# 51.net
KiCad netlist of a schematic drawn in EasyEDA Pro
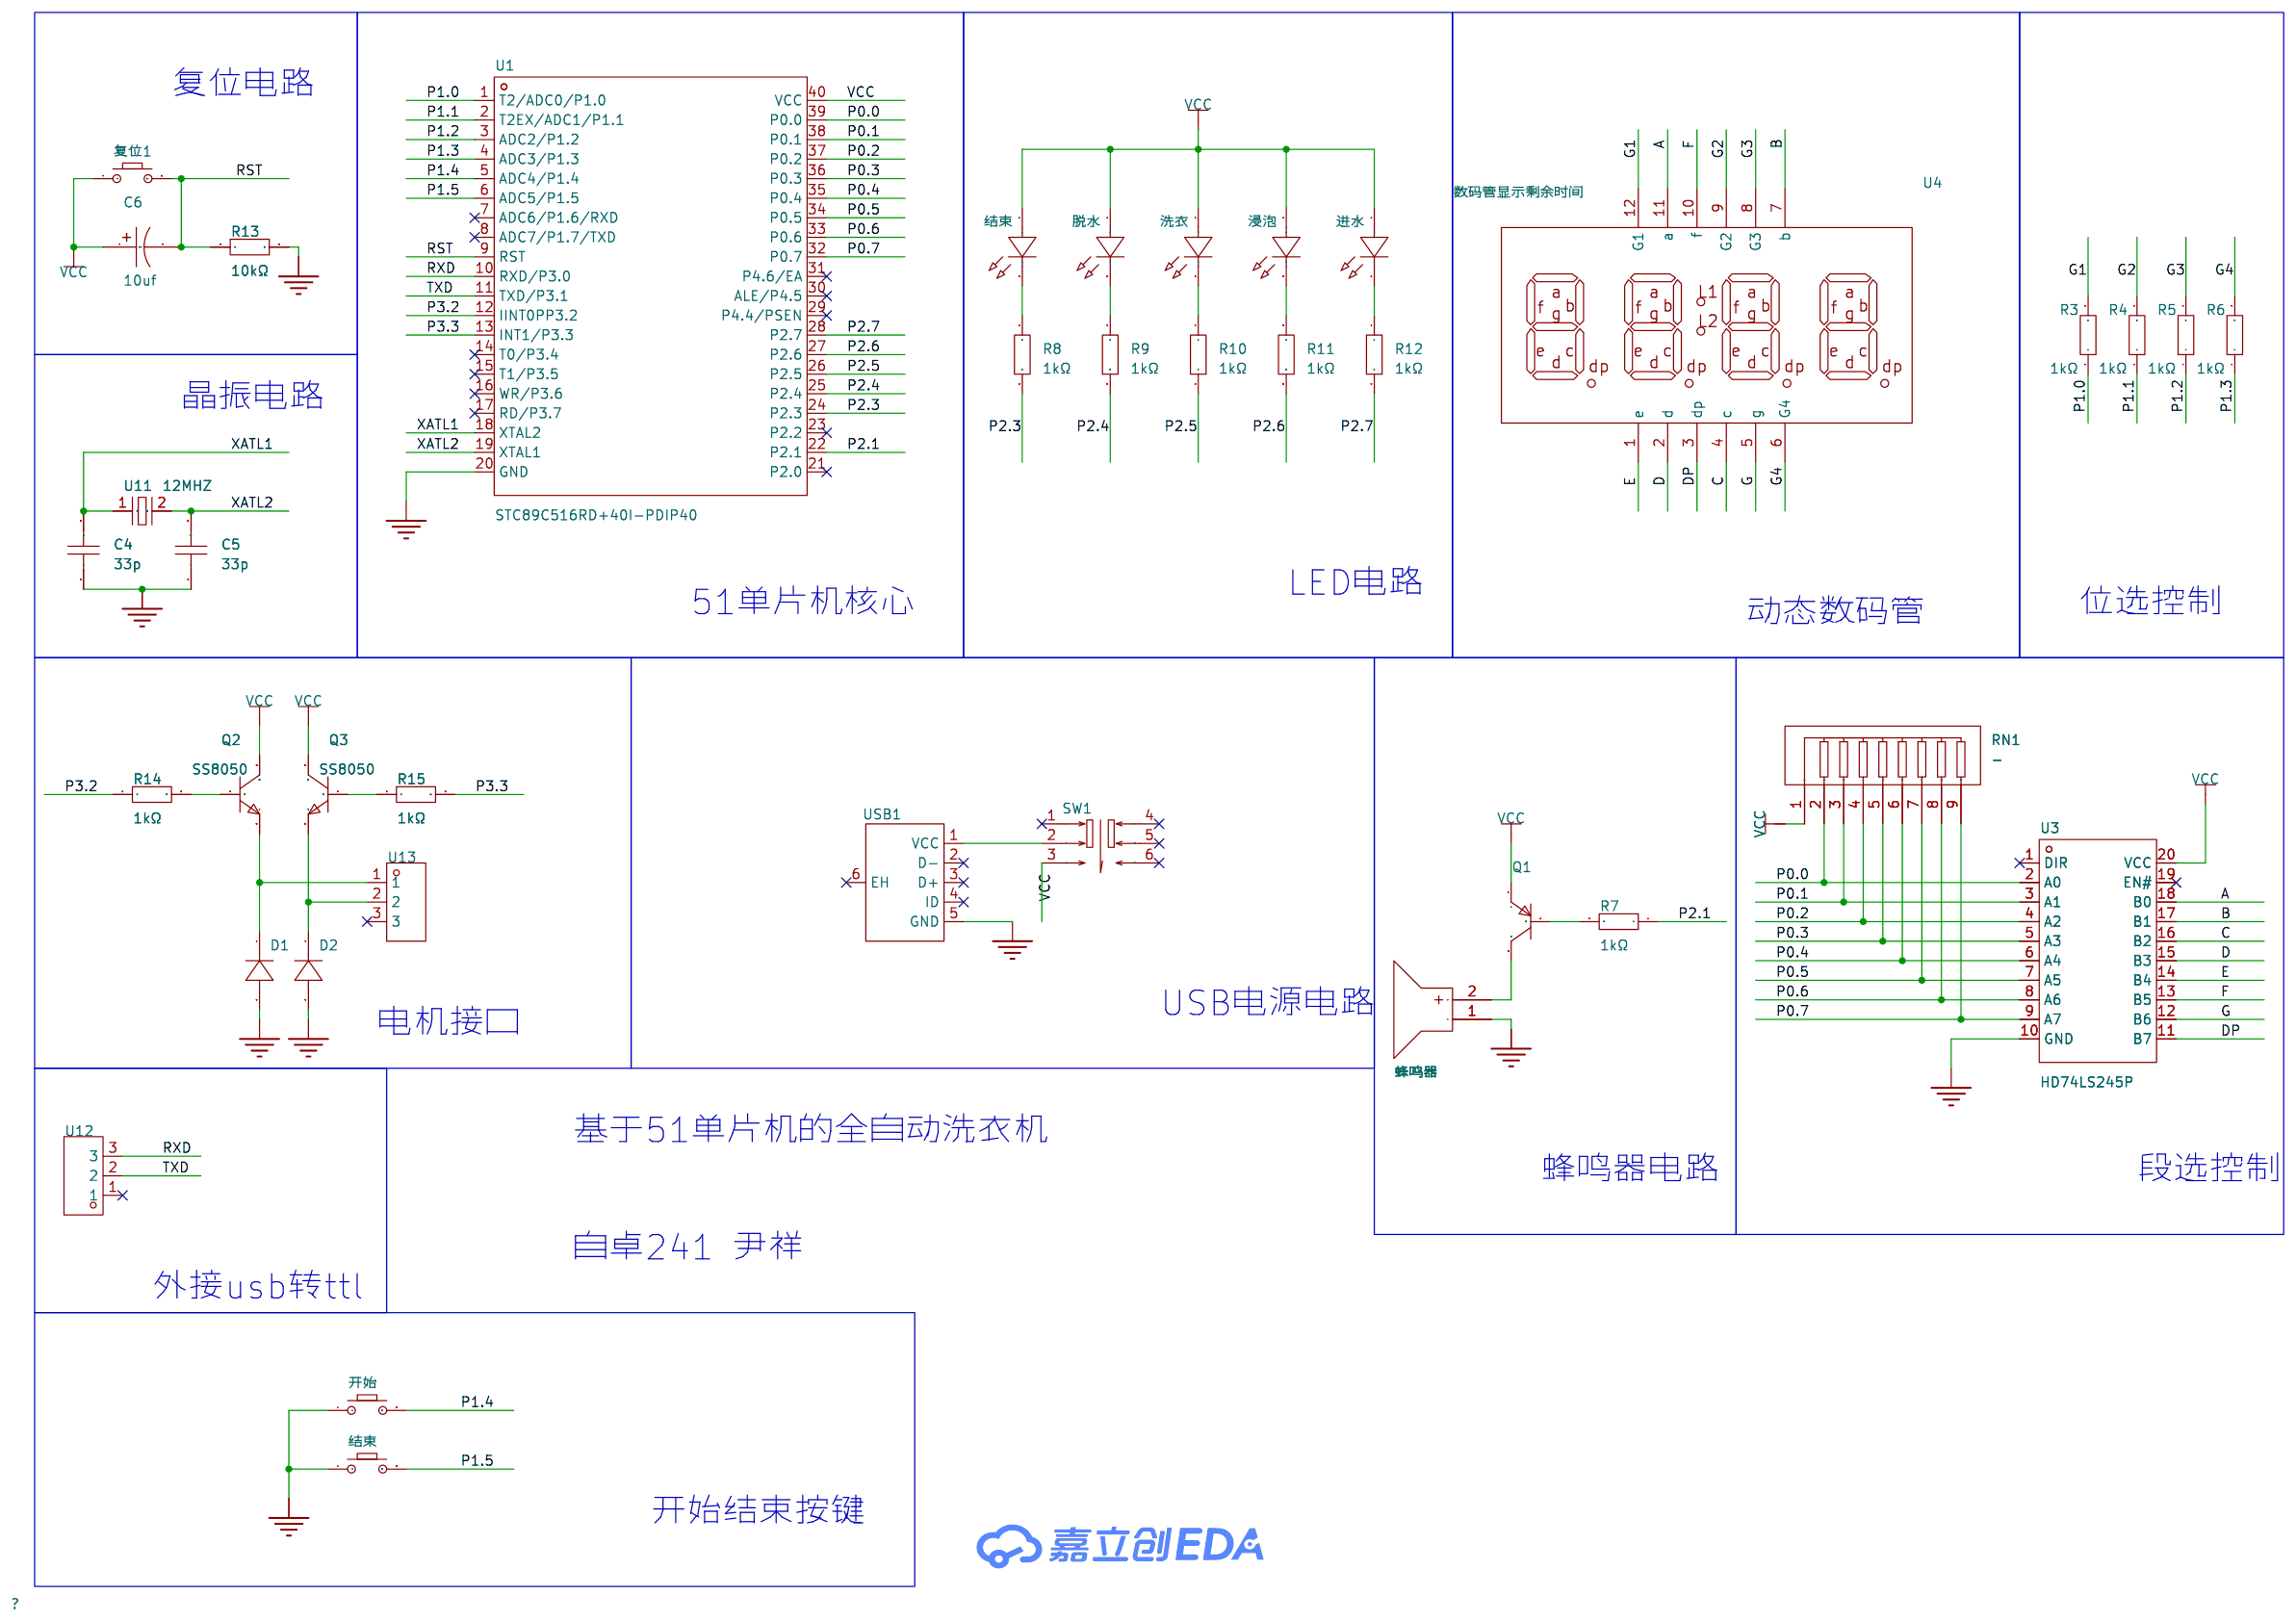
[diagram p0: schematic sheet]

(export (version "E")
  (design (tool "Eeschema 10.0.6"))
  (components
    (comp (ref "C4")
      (value "33p")
      (footprint "easyedapro:CAP-TH_L10.0-W4.5-P7.50-D0.6")
      (description "容值:-;额定电压:-;")
      (fields (field (name "Manufacturer Part") "250V 0.1uF 5% CBB电容"))
      (libsource (lib "easyedapro") (part "250V 0.1UF 5% CBBCapacitor"))
    )
    (comp (ref "C5")
      (value "33p")
      (footprint "easyedapro:CAP-TH_L10.0-W4.5-P7.50-D0.6")
      (description "容值:-;额定电压:-;")
      (fields (field (name "Manufacturer Part") "250V 0.1uF 5% CBB电容"))
      (libsource (lib "easyedapro") (part "250V 0.1UF 5% CBBCapacitor"))
    )
    (comp (ref "C6")
      (value "10uf")
      (footprint "easyedapro:CAP-TH_BD10.0-P5.00-D0.6-FD")
      (libsource (lib "easyedapro") (part "LF221M1HBKJ1013VGN"))
    )
    (comp (ref "D1")
      (value "~")
      (footprint "easyedapro:DO_1N4007")
      (libsource (lib "easyedapro") (part "D_1N4007"))
    )
    (comp (ref "D2")
      (value "~")
      (footprint "easyedapro:DO_1N4007")
      (libsource (lib "easyedapro") (part "D_1N4007"))
    )
    (comp (ref "Q1")
      (value "~")
      (footprint "easyedapro:S8550P_TO-92")
      (libsource (lib "easyedapro") (part "S8550_TO_PNP"))
    )
    (comp (ref "Q2")
      (value "SS8050")
      (footprint "easyedapro:SOT-23-3_L2.9-W1.3-P1.90-LS2.4-BR")
      (description "晶体管类型:NPN;集电极电流(Ic):1.5A;集射极击穿电压(Vceo):25V;功率(Pd):300mW;直流电流增益(hFE@Ic,Vce):200@800mA,1V;")
      (fields (field (name "Manufacturer") "CJ(江苏长电/长晶)"))
      (libsource (lib "easyedapro") (part "SS8050_C2150"))
    )
    (comp (ref "Q3")
      (value "SS8050")
      (footprint "easyedapro:SOT-23-3_L2.9-W1.3-P1.90-LS2.4-BR")
      (description "晶体管类型:NPN;集电极电流(Ic):1.5A;集射极击穿电压(Vceo):25V;功率(Pd):300mW;直流电流增益(hFE@Ic,Vce):200@800mA,1V;")
      (fields (field (name "Manufacturer") "CJ(江苏长电/长晶)"))
      (libsource (lib "easyedapro") (part "SS8050_C2150"))
    )
    (comp (ref "R3")
      (value "1kΩ")
      (footprint "easyedapro:Res_1/8W")
      (libsource (lib "easyedapro") (part "电阻"))
    )
    (comp (ref "R4")
      (value "1kΩ")
      (footprint "easyedapro:Res_1/8W")
      (libsource (lib "easyedapro") (part "电阻"))
    )
    (comp (ref "R5")
      (value "1kΩ")
      (footprint "easyedapro:Res_1/8W")
      (libsource (lib "easyedapro") (part "电阻"))
    )
    (comp (ref "R6")
      (value "1kΩ")
      (footprint "easyedapro:Res_1/8W")
      (libsource (lib "easyedapro") (part "电阻"))
    )
    (comp (ref "R7")
      (value "1kΩ")
      (footprint "easyedapro:Res_1/8W")
      (libsource (lib "easyedapro") (part "电阻"))
    )
    (comp (ref "R8")
      (value "1kΩ")
      (footprint "easyedapro:Res_1/8W")
      (libsource (lib "easyedapro") (part "电阻"))
    )
    (comp (ref "R9")
      (value "1kΩ")
      (footprint "easyedapro:Res_1/8W")
      (libsource (lib "easyedapro") (part "电阻"))
    )
    (comp (ref "R10")
      (value "1kΩ")
      (footprint "easyedapro:Res_1/8W")
      (libsource (lib "easyedapro") (part "电阻"))
    )
    (comp (ref "R11")
      (value "1kΩ")
      (footprint "easyedapro:Res_1/8W")
      (libsource (lib "easyedapro") (part "电阻"))
    )
    (comp (ref "R12")
      (value "1kΩ")
      (footprint "easyedapro:Res_1/8W")
      (libsource (lib "easyedapro") (part "电阻"))
    )
    (comp (ref "R13")
      (value "10kΩ")
      (footprint "easyedapro:Res_1/8W")
      (libsource (lib "easyedapro") (part "电阻"))
    )
    (comp (ref "R14")
      (value "1kΩ")
      (footprint "easyedapro:Res_1/8W")
      (libsource (lib "easyedapro") (part "电阻"))
    )
    (comp (ref "R15")
      (value "1kΩ")
      (footprint "easyedapro:Res_1/8W")
      (libsource (lib "easyedapro") (part "电阻"))
    )
    (comp (ref "RN1")
      (value "-")
      (footprint "easyedapro:RES-ARRAY-TH_9P-P2.54-D1.0")
      (description "电阻器数:-;阻值:-;单个元件功率:-;")
      (fields (field (name "Manufacturer Part") "排阻 10 K 5%"))
      (libsource (lib "easyedapro") (part "10 K 5%"))
    )
    (comp (ref "SW1")
      (value "SP-2212")
      (footprint "easyedapro:SW-TH_6P-L7.2-W7.2-P2.00-LS5.0")
      (description "电路结构:双刀双掷;自锁/无锁:自锁;安装方式:直插;触点电流:100mA;额定电压 (DC):30V;作用力:230gf;机械寿命:1.2万次;")
      (fields (field (name "Manufacturer") "RISHENG(日昇)"))
      (libsource (lib "easyedapro") (part "SP-2212"))
    )
    (comp (ref "U1")
      (value "STC89C516RD+40I-PDIP40")
      (footprint "easyedapro:DIP-40_L52.3-W13.9-P2.54-LS15.2-BL")
      (description "CPU内核:51系列;程序存储容量:61KB;RAM总容量:1.25KB;GPIO端口数量:35;工作电压范围:3.5V~5.5V;CPU最大主频:-;程序存储器类型:FLASH;")
      (fields (field (name "Manufacturer") "STC(宏晶)"))
      (libsource (lib "easyedapro") (part "STC89C516RD+40I-PDIP40"))
    )
    (comp (ref "U3")
      (value "HD74LS245P")
      (footprint "easyedapro:DIP-20_L26.8-W6.4-P2.54-LS7.6-BL")
      (fields (field (name "Manufacturer") "RENESAS(瑞萨)/IDT"))
      (libsource (lib "easyedapro") (part "HD74LS245P"))
    )
    (comp (ref "U4")
      (value "数码管显示剩余时间")
      (footprint "easyedapro:LED-SEG-TH_12P-L32.1-W10.0-P12.7-S7.62-BL")
      (libsource (lib "easyedapro") (part "0.28 4位 数码管"))
    )
    (comp (ref "U11")
      (value "12MHZ")
      (footprint "easyedapro:HC-49S_L11.0-W4.7-P4.88")
      (libsource (lib "easyedapro") (part "直插晶振"))
    )
    (comp (ref "U12")
      (value "2.54MM间距单排插针3P/高度11mm")
      (footprint "easyedapro:HDR-TH_3P-P2.54-V-M")
      (libsource (lib "easyedapro") (part "2.54MM间距单排插针3P/高度11MM"))
    )
    (comp (ref "U13")
      (value "2.54MM间距单排插针3P/高度11mm")
      (footprint "easyedapro:HDR-TH_3P-P2.54-V-M")
      (libsource (lib "easyedapro") (part "2.54MM间距单排插针3P/高度11MM"))
    )
    (comp (ref "USB1")
      (value "~")
      (footprint "easyedapro:USB_Micro")
      (libsource (lib "easyedapro") (part "USB_Micro"))
    )
    (comp (ref "图书馆1")
      (value "脱水")
      (footprint "easyedapro:LED-TH_BD3.0-P2.54-FD")
      (libsource (lib "easyedapro") (part "3MMFIR"))
    )
    (comp (ref "复位1")
      (value "~")
      (footprint "easyedapro:Key_TH_3.5x6x4.3")
      (libsource (lib "easyedapro") (part "Key_TH_3.5x6x4.3"))
    )
    (comp (ref "学生宿舍1")
      (value "洗衣")
      (footprint "easyedapro:LED-TH_BD3.0-P2.54-FD")
      (libsource (lib "easyedapro") (part "3MMFIR"))
    )
    (comp (ref "开始")
      (value "~")
      (footprint "easyedapro:Key_TH_3.5x6x4.3")
      (libsource (lib "easyedapro") (part "Key_TH_3.5x6x4.3"))
    )
    (comp (ref "打铃1")
      (value "蜂鸣器")
      (footprint "easyedapro:BUZ-TH_BD12.0-P6.00-D0.9-RD")
      (fields (field (name "Manufacturer Part") "打铃"))
      (libsource (lib "easyedapro") (part "BUZZER"))
    )
    (comp (ref "教十楼1")
      (value "浸泡")
      (footprint "easyedapro:LED-TH_BD3.0-P2.54-FD")
      (libsource (lib "easyedapro") (part "3MMFIR"))
    )
    (comp (ref "结束")
      (value "~")
      (footprint "easyedapro:Key_TH_3.5x6x4.3")
      (libsource (lib "easyedapro") (part "Key_TH_3.5x6x4.3"))
    )
    (comp (ref "综合南楼1")
      (value "进水")
      (footprint "easyedapro:LED-TH_BD3.0-P2.54-FD")
      (libsource (lib "easyedapro") (part "3MMFIR"))
    )
    (comp (ref "路灯1")
      (value "结束")
      (footprint "easyedapro:LED-TH_BD3.0-P2.54-FD")
      (libsource (lib "easyedapro") (part "3MMFIR"))
    )
  )
  (nets
    (net (code "1") (name "/A") (class "Default")
      (node (ref "U3") (pin "18") (pinfunction "B0_18") (pintype "unspecified"))
      (node (ref "U4") (pin "11") (pinfunction "a_11") (pintype "input"))
    )
    (net (code "2") (name "/B") (class "Default")
      (node (ref "U3") (pin "17") (pinfunction "B1_17") (pintype "unspecified"))
      (node (ref "U4") (pin "7") (pinfunction "b_7") (pintype "input"))
    )
    (net (code "3") (name "/C") (class "Default")
      (node (ref "U3") (pin "16") (pinfunction "B2_16") (pintype "unspecified"))
      (node (ref "U4") (pin "4") (pinfunction "c_4") (pintype "input"))
    )
    (net (code "4") (name "/D") (class "Default")
      (node (ref "U3") (pin "15") (pinfunction "B3_15") (pintype "unspecified"))
      (node (ref "U4") (pin "2") (pinfunction "d_2") (pintype "input"))
    )
    (net (code "5") (name "/DP") (class "Default")
      (node (ref "U3") (pin "11") (pinfunction "B7_11") (pintype "unspecified"))
      (node (ref "U4") (pin "3") (pinfunction "dp_3") (pintype "input"))
    )
    (net (code "6") (name "/E") (class "Default")
      (node (ref "U3") (pin "14") (pinfunction "B4_14") (pintype "unspecified"))
      (node (ref "U4") (pin "1") (pinfunction "e_1") (pintype "input"))
    )
    (net (code "7") (name "/F") (class "Default")
      (node (ref "U3") (pin "13") (pinfunction "B5_13") (pintype "unspecified"))
      (node (ref "U4") (pin "10") (pinfunction "f_10") (pintype "input"))
    )
    (net (code "8") (name "/G") (class "Default")
      (node (ref "U3") (pin "12") (pinfunction "B6_12") (pintype "unspecified"))
      (node (ref "U4") (pin "5") (pinfunction "g_5") (pintype "input"))
    )
    (net (code "9") (name "/G1") (class "Default")
      (node (ref "R3") (pin "2") (pinfunction "2_2") (pintype "input"))
      (node (ref "U4") (pin "12") (pinfunction "G1_12") (pintype "input"))
    )
    (net (code "10") (name "/G2") (class "Default")
      (node (ref "R4") (pin "2") (pinfunction "2_2") (pintype "input"))
      (node (ref "U4") (pin "9") (pinfunction "G2_9") (pintype "input"))
    )
    (net (code "11") (name "/G3") (class "Default")
      (node (ref "R5") (pin "2") (pinfunction "2_2") (pintype "input"))
      (node (ref "U4") (pin "8") (pinfunction "G3_8") (pintype "input"))
    )
    (net (code "12") (name "/G4") (class "Default")
      (node (ref "R6") (pin "2") (pinfunction "2_2") (pintype "input"))
      (node (ref "U4") (pin "6") (pinfunction "G4_6") (pintype "input"))
    )
    (net (code "13") (name "/P0.0") (class "Default")
      (node (ref "RN1") (pin "2") (pinfunction "2_2") (pintype "input"))
      (node (ref "U1") (pin "39") (pinfunction "P0.0_39") (pintype "unspecified"))
      (node (ref "U3") (pin "2") (pinfunction "A0_2") (pintype "unspecified"))
    )
    (net (code "14") (name "/P0.1") (class "Default")
      (node (ref "RN1") (pin "3") (pinfunction "3_3") (pintype "input"))
      (node (ref "U1") (pin "38") (pinfunction "P0.1_38") (pintype "unspecified"))
      (node (ref "U3") (pin "3") (pinfunction "A1_3") (pintype "unspecified"))
    )
    (net (code "15") (name "/P0.2") (class "Default")
      (node (ref "RN1") (pin "4") (pinfunction "4_4") (pintype "input"))
      (node (ref "U1") (pin "37") (pinfunction "P0.2_37") (pintype "unspecified"))
      (node (ref "U3") (pin "4") (pinfunction "A2_4") (pintype "unspecified"))
    )
    (net (code "16") (name "/P0.3") (class "Default")
      (node (ref "RN1") (pin "5") (pinfunction "5_5") (pintype "input"))
      (node (ref "U1") (pin "36") (pinfunction "P0.3_36") (pintype "unspecified"))
      (node (ref "U3") (pin "5") (pinfunction "A3_5") (pintype "unspecified"))
    )
    (net (code "17") (name "/P0.4") (class "Default")
      (node (ref "RN1") (pin "6") (pinfunction "6_6") (pintype "input"))
      (node (ref "U1") (pin "35") (pinfunction "P0.4_35") (pintype "unspecified"))
      (node (ref "U3") (pin "6") (pinfunction "A4_6") (pintype "unspecified"))
    )
    (net (code "18") (name "/P0.5") (class "Default")
      (node (ref "RN1") (pin "7") (pinfunction "7_7") (pintype "input"))
      (node (ref "U1") (pin "34") (pinfunction "P0.5_34") (pintype "unspecified"))
      (node (ref "U3") (pin "7") (pinfunction "A5_7") (pintype "unspecified"))
    )
    (net (code "19") (name "/P0.6") (class "Default")
      (node (ref "RN1") (pin "8") (pinfunction "8_8") (pintype "input"))
      (node (ref "U1") (pin "33") (pinfunction "P0.6_33") (pintype "unspecified"))
      (node (ref "U3") (pin "8") (pinfunction "A6_8") (pintype "unspecified"))
    )
    (net (code "20") (name "/P0.7") (class "Default")
      (node (ref "RN1") (pin "9") (pinfunction "9_9") (pintype "input"))
      (node (ref "U1") (pin "32") (pinfunction "P0.7_32") (pintype "unspecified"))
      (node (ref "U3") (pin "9") (pinfunction "A7_9") (pintype "unspecified"))
    )
    (net (code "21") (name "/P1.0") (class "Default")
      (node (ref "R3") (pin "1") (pinfunction "1_1") (pintype "input"))
      (node (ref "U1") (pin "1") (pinfunction "T2/ADC0/P1.0_1") (pintype "unspecified"))
    )
    (net (code "22") (name "/P1.1") (class "Default")
      (node (ref "R4") (pin "1") (pinfunction "1_1") (pintype "input"))
      (node (ref "U1") (pin "2") (pinfunction "T2EX/ADC1/P1.1_2") (pintype "unspecified"))
    )
    (net (code "23") (name "/P1.2") (class "Default")
      (node (ref "R5") (pin "1") (pinfunction "1_1") (pintype "input"))
      (node (ref "U1") (pin "3") (pinfunction "ADC2/P1.2_3") (pintype "unspecified"))
    )
    (net (code "24") (name "/P1.3") (class "Default")
      (node (ref "R6") (pin "1") (pinfunction "1_1") (pintype "input"))
      (node (ref "U1") (pin "4") (pinfunction "ADC3/P1.3_4") (pintype "unspecified"))
    )
    (net (code "25") (name "/P1.4") (class "Default")
      (node (ref "U1") (pin "5") (pinfunction "ADC4/P1.4_5") (pintype "unspecified"))
      (node (ref "开始") (pin "B") (pinfunction "B_B") (pintype "input"))
    )
    (net (code "26") (name "/P1.5") (class "Default")
      (node (ref "U1") (pin "6") (pinfunction "ADC5/P1.5_6") (pintype "unspecified"))
      (node (ref "结束") (pin "B") (pinfunction "B_B") (pintype "input"))
    )
    (net (code "27") (name "/P2.1") (class "Default")
      (node (ref "R7") (pin "1") (pinfunction "1_1") (pintype "input"))
      (node (ref "U1") (pin "22") (pinfunction "P2.1_22") (pintype "unspecified"))
    )
    (net (code "28") (name "/P2.3") (class "Default")
      (node (ref "R8") (pin "2") (pinfunction "2_2") (pintype "input"))
      (node (ref "U1") (pin "24") (pinfunction "P2.3_24") (pintype "unspecified"))
    )
    (net (code "29") (name "/P2.4") (class "Default")
      (node (ref "R9") (pin "2") (pinfunction "2_2") (pintype "input"))
      (node (ref "U1") (pin "25") (pinfunction "P2.4_25") (pintype "unspecified"))
    )
    (net (code "30") (name "/P2.5") (class "Default")
      (node (ref "R10") (pin "2") (pinfunction "2_2") (pintype "input"))
      (node (ref "U1") (pin "26") (pinfunction "P2.5_26") (pintype "unspecified"))
    )
    (net (code "31") (name "/P2.6") (class "Default")
      (node (ref "R11") (pin "2") (pinfunction "2_2") (pintype "input"))
      (node (ref "U1") (pin "27") (pinfunction "P2.6_27") (pintype "unspecified"))
    )
    (net (code "32") (name "/P2.7") (class "Default")
      (node (ref "R12") (pin "2") (pinfunction "2_2") (pintype "input"))
      (node (ref "U1") (pin "28") (pinfunction "P2.7_28") (pintype "unspecified"))
    )
    (net (code "33") (name "/P3.2") (class "Default")
      (node (ref "R14") (pin "1") (pinfunction "1_1") (pintype "input"))
      (node (ref "U1") (pin "12") (pinfunction "IINT0PP3.2_12") (pintype "unspecified"))
    )
    (net (code "34") (name "/P3.3") (class "Default")
      (node (ref "R15") (pin "2") (pinfunction "2_2") (pintype "input"))
      (node (ref "U1") (pin "13") (pinfunction "INT1/P3.3_13") (pintype "unspecified"))
    )
    (net (code "35") (name "/RST") (class "Default")
      (node (ref "C6") (pin "2") (pinfunction "2_2") (pintype "unspecified"))
      (node (ref "R13") (pin "1") (pinfunction "1_1") (pintype "input"))
      (node (ref "U1") (pin "9") (pinfunction "RST_9") (pintype "unspecified"))
      (node (ref "复位1") (pin "B") (pinfunction "B_B") (pintype "input"))
    )
    (net (code "36") (name "/RXD") (class "Default")
      (node (ref "U1") (pin "10") (pinfunction "RXD/P3.0_10") (pintype "unspecified"))
      (node (ref "U12") (pin "3") (pinfunction "3_3") (pintype "unspecified"))
    )
    (net (code "37") (name "/TXD") (class "Default")
      (node (ref "U1") (pin "11") (pinfunction "TXD/P3.1_11") (pintype "unspecified"))
      (node (ref "U12") (pin "2") (pinfunction "2_2") (pintype "unspecified"))
    )
    (net (code "38") (name "/XATL1") (class "Default")
      (node (ref "C4") (pin "2") (pinfunction "2_2") (pintype "unspecified"))
      (node (ref "U1") (pin "18") (pinfunction "XTAL2_18") (pintype "unspecified"))
      (node (ref "U11") (pin "1") (pinfunction "1_1") (pintype "input"))
    )
    (net (code "39") (name "/XATL2") (class "Default")
      (node (ref "C5") (pin "2") (pinfunction "2_2") (pintype "unspecified"))
      (node (ref "U1") (pin "19") (pinfunction "XTAL1_19") (pintype "unspecified"))
      (node (ref "U11") (pin "2") (pinfunction "GND_2") (pintype "input"))
    )
    (net (code "40") (name "GND") (class "Default")
      (node (ref "C4") (pin "1") (pinfunction "1_1") (pintype "unspecified"))
      (node (ref "C5") (pin "1") (pinfunction "1_1") (pintype "unspecified"))
      (node (ref "D1") (pin "2") (pinfunction "A_2") (pintype "input"))
      (node (ref "D2") (pin "2") (pinfunction "A_2") (pintype "input"))
      (node (ref "R13") (pin "2") (pinfunction "2_2") (pintype "input"))
      (node (ref "U1") (pin "20") (pinfunction "GND_20") (pintype "unspecified"))
      (node (ref "U3") (pin "10") (pinfunction "GND_10") (pintype "unspecified"))
      (node (ref "USB1") (pin "5") (pinfunction "GND_5") (pintype "input"))
      (node (ref "开始") (pin "A") (pinfunction "A_A") (pintype "input"))
      (node (ref "打铃1") (pin "1") (pinfunction "-_1") (pintype "unspecified"))
      (node (ref "结束") (pin "A") (pinfunction "A_A") (pintype "input"))
    )
    (net (code "41") (name "Net-(D1-K)") (class "Default")
      (node (ref "D1") (pin "1") (pinfunction "K_1") (pintype "input"))
      (node (ref "Q2") (pin "2") (pinfunction "E_2") (pintype "unspecified"))
      (node (ref "U13") (pin "1") (pinfunction "1_1") (pintype "unspecified"))
    )
    (net (code "42") (name "Net-(D2-K)") (class "Default")
      (node (ref "D2") (pin "1") (pinfunction "K_1") (pintype "input"))
      (node (ref "Q3") (pin "2") (pinfunction "E_2") (pintype "unspecified"))
      (node (ref "U13") (pin "2") (pinfunction "2_2") (pintype "unspecified"))
    )
    (net (code "43") (name "Net-(Q1-B)") (class "Default")
      (node (ref "Q1") (pin "2") (pinfunction "B_2") (pintype "input"))
      (node (ref "R7") (pin "2") (pinfunction "2_2") (pintype "input"))
    )
    (net (code "44") (name "Net-(Q1-C)") (class "Default")
      (node (ref "Q1") (pin "3") (pinfunction "C_3") (pintype "input"))
      (node (ref "打铃1") (pin "2") (pinfunction "+_2") (pintype "unspecified"))
    )
    (net (code "45") (name "Net-(Q2-B)") (class "Default")
      (node (ref "Q2") (pin "1") (pinfunction "B_1") (pintype "unspecified"))
      (node (ref "R14") (pin "2") (pinfunction "2_2") (pintype "input"))
    )
    (net (code "46") (name "Net-(Q3-B)") (class "Default")
      (node (ref "Q3") (pin "1") (pinfunction "B_1") (pintype "unspecified"))
      (node (ref "R15") (pin "1") (pinfunction "1_1") (pintype "input"))
    )
    (net (code "47") (name "Net-(USB1-VCC)") (class "Default")
      (node (ref "SW1") (pin "2") (pinfunction "2_2") (pintype "unspecified"))
      (node (ref "USB1") (pin "1") (pinfunction "VCC_1") (pintype "input"))
    )
    (net (code "48") (name "Net-(图书馆1-K)") (class "Default")
      (node (ref "R9") (pin "1") (pinfunction "1_1") (pintype "input"))
      (node (ref "图书馆1") (pin "2") (pinfunction "K_2") (pintype "unspecified"))
    )
    (net (code "49") (name "Net-(学生宿舍1-K)") (class "Default")
      (node (ref "R10") (pin "1") (pinfunction "1_1") (pintype "input"))
      (node (ref "学生宿舍1") (pin "2") (pinfunction "K_2") (pintype "unspecified"))
    )
    (net (code "50") (name "Net-(教十楼1-K)") (class "Default")
      (node (ref "R11") (pin "1") (pinfunction "1_1") (pintype "input"))
      (node (ref "教十楼1") (pin "2") (pinfunction "K_2") (pintype "unspecified"))
    )
    (net (code "51") (name "Net-(综合南楼1-K)") (class "Default")
      (node (ref "R12") (pin "1") (pinfunction "1_1") (pintype "input"))
      (node (ref "综合南楼1") (pin "2") (pinfunction "K_2") (pintype "unspecified"))
    )
    (net (code "52") (name "Net-(路灯1-K)") (class "Default")
      (node (ref "R8") (pin "1") (pinfunction "1_1") (pintype "input"))
      (node (ref "路灯1") (pin "2") (pinfunction "K_2") (pintype "unspecified"))
    )
    (net (code "53") (name "VCC") (class "Default")
      (node (ref "C6") (pin "1") (pinfunction "1_1") (pintype "unspecified"))
      (node (ref "Q1") (pin "1") (pinfunction "E_1") (pintype "input"))
      (node (ref "Q2") (pin "3") (pinfunction "C_3") (pintype "unspecified"))
      (node (ref "Q3") (pin "3") (pinfunction "C_3") (pintype "unspecified"))
      (node (ref "RN1") (pin "1") (pinfunction "1_1") (pintype "input"))
      (node (ref "SW1") (pin "3") (pinfunction "3_3") (pintype "unspecified"))
      (node (ref "U1") (pin "40") (pinfunction "VCC_40") (pintype "unspecified"))
      (node (ref "U3") (pin "20") (pinfunction "VCC_20") (pintype "unspecified"))
      (node (ref "图书馆1") (pin "1") (pinfunction "A_1") (pintype "unspecified"))
      (node (ref "复位1") (pin "A") (pinfunction "A_A") (pintype "input"))
      (node (ref "学生宿舍1") (pin "1") (pinfunction "A_1") (pintype "unspecified"))
      (node (ref "教十楼1") (pin "1") (pinfunction "A_1") (pintype "unspecified"))
      (node (ref "综合南楼1") (pin "1") (pinfunction "A_1") (pintype "unspecified"))
      (node (ref "路灯1") (pin "1") (pinfunction "A_1") (pintype "unspecified"))
    )
    (net (code "54") (name "unconnected-(SW1-Pad1)") (class "Default")
      (node (ref "SW1") (pin "1") (pinfunction "1_1") (pintype "unspecified+no_connect"))
    )
    (net (code "55") (name "unconnected-(SW1-Pad4)") (class "Default")
      (node (ref "SW1") (pin "4") (pinfunction "4_4") (pintype "unspecified+no_connect"))
    )
    (net (code "56") (name "unconnected-(SW1-Pad5)") (class "Default")
      (node (ref "SW1") (pin "5") (pinfunction "5_5") (pintype "unspecified+no_connect"))
    )
    (net (code "57") (name "unconnected-(SW1-Pad6)") (class "Default")
      (node (ref "SW1") (pin "6") (pinfunction "6_6") (pintype "unspecified+no_connect"))
    )
    (net (code "58") (name "unconnected-(U1-ADC6{slash}P1.6{slash}RXD-Pad7)") (class "Default")
      (node (ref "U1") (pin "7") (pinfunction "ADC6/P1.6/RXD_7") (pintype "unspecified+no_connect"))
    )
    (net (code "59") (name "unconnected-(U1-ADC7{slash}P1.7{slash}TXD-Pad8)") (class "Default")
      (node (ref "U1") (pin "8") (pinfunction "ADC7/P1.7/TXD_8") (pintype "unspecified+no_connect"))
    )
    (net (code "60") (name "unconnected-(U1-ALE{slash}P4.5-Pad30)") (class "Default")
      (node (ref "U1") (pin "30") (pinfunction "ALE/P4.5_30") (pintype "unspecified+no_connect"))
    )
    (net (code "61") (name "unconnected-(U1-P2.0-Pad21)") (class "Default")
      (node (ref "U1") (pin "21") (pinfunction "P2.0_21") (pintype "unspecified+no_connect"))
    )
    (net (code "62") (name "unconnected-(U1-P2.2-Pad23)") (class "Default")
      (node (ref "U1") (pin "23") (pinfunction "P2.2_23") (pintype "unspecified+no_connect"))
    )
    (net (code "63") (name "unconnected-(U1-P4.4{slash}PSEN-Pad29)") (class "Default")
      (node (ref "U1") (pin "29") (pinfunction "P4.4/PSEN_29") (pintype "unspecified+no_connect"))
    )
    (net (code "64") (name "unconnected-(U1-P4.6{slash}EA-Pad31)") (class "Default")
      (node (ref "U1") (pin "31") (pinfunction "P4.6/EA_31") (pintype "unspecified+no_connect"))
    )
    (net (code "65") (name "unconnected-(U1-RD{slash}P3.7-Pad17)") (class "Default")
      (node (ref "U1") (pin "17") (pinfunction "RD/P3.7_17") (pintype "unspecified+no_connect"))
    )
    (net (code "66") (name "unconnected-(U1-T0{slash}P3.4-Pad14)") (class "Default")
      (node (ref "U1") (pin "14") (pinfunction "T0/P3.4_14") (pintype "unspecified+no_connect"))
    )
    (net (code "67") (name "unconnected-(U1-T1{slash}P3.5-Pad15)") (class "Default")
      (node (ref "U1") (pin "15") (pinfunction "T1/P3.5_15") (pintype "unspecified+no_connect"))
    )
    (net (code "68") (name "unconnected-(U1-WR{slash}P3.6-Pad16)") (class "Default")
      (node (ref "U1") (pin "16") (pinfunction "WR/P3.6_16") (pintype "unspecified+no_connect"))
    )
    (net (code "69") (name "unconnected-(U3-DIR-Pad1)") (class "Default")
      (node (ref "U3") (pin "1") (pinfunction "DIR_1") (pintype "unspecified+no_connect"))
    )
    (net (code "70") (name "unconnected-(U3-EN#-Pad19)") (class "Default")
      (node (ref "U3") (pin "19") (pinfunction "EN#_19") (pintype "unspecified+no_connect"))
    )
    (net (code "71") (name "unconnected-(U12-Pad1)") (class "Default")
      (node (ref "U12") (pin "1") (pinfunction "1_1") (pintype "unspecified+no_connect"))
    )
    (net (code "72") (name "unconnected-(U13-Pad3)") (class "Default")
      (node (ref "U13") (pin "3") (pinfunction "3_3") (pintype "unspecified+no_connect"))
    )
    (net (code "73") (name "unconnected-(USB1-D+-Pad3)") (class "Default")
      (node (ref "USB1") (pin "3") (pinfunction "D+_3") (pintype "input+no_connect"))
    )
    (net (code "74") (name "unconnected-(USB1-D--Pad2)") (class "Default")
      (node (ref "USB1") (pin "2") (pinfunction "D-_2") (pintype "input+no_connect"))
    )
    (net (code "75") (name "unconnected-(USB1-EH-Pad6)") (class "Default")
      (node (ref "USB1") (pin "6") (pinfunction "EH_6") (pintype "input+no_connect"))
    )
    (net (code "76") (name "unconnected-(USB1-ID-Pad4)") (class "Default")
      (node (ref "USB1") (pin "4") (pinfunction "ID_4") (pintype "input+no_connect"))
    )
  )
)
